# ProPrj_auduino__2024-11-21.net
KiCad netlist of a schematic drawn in EasyEDA Pro
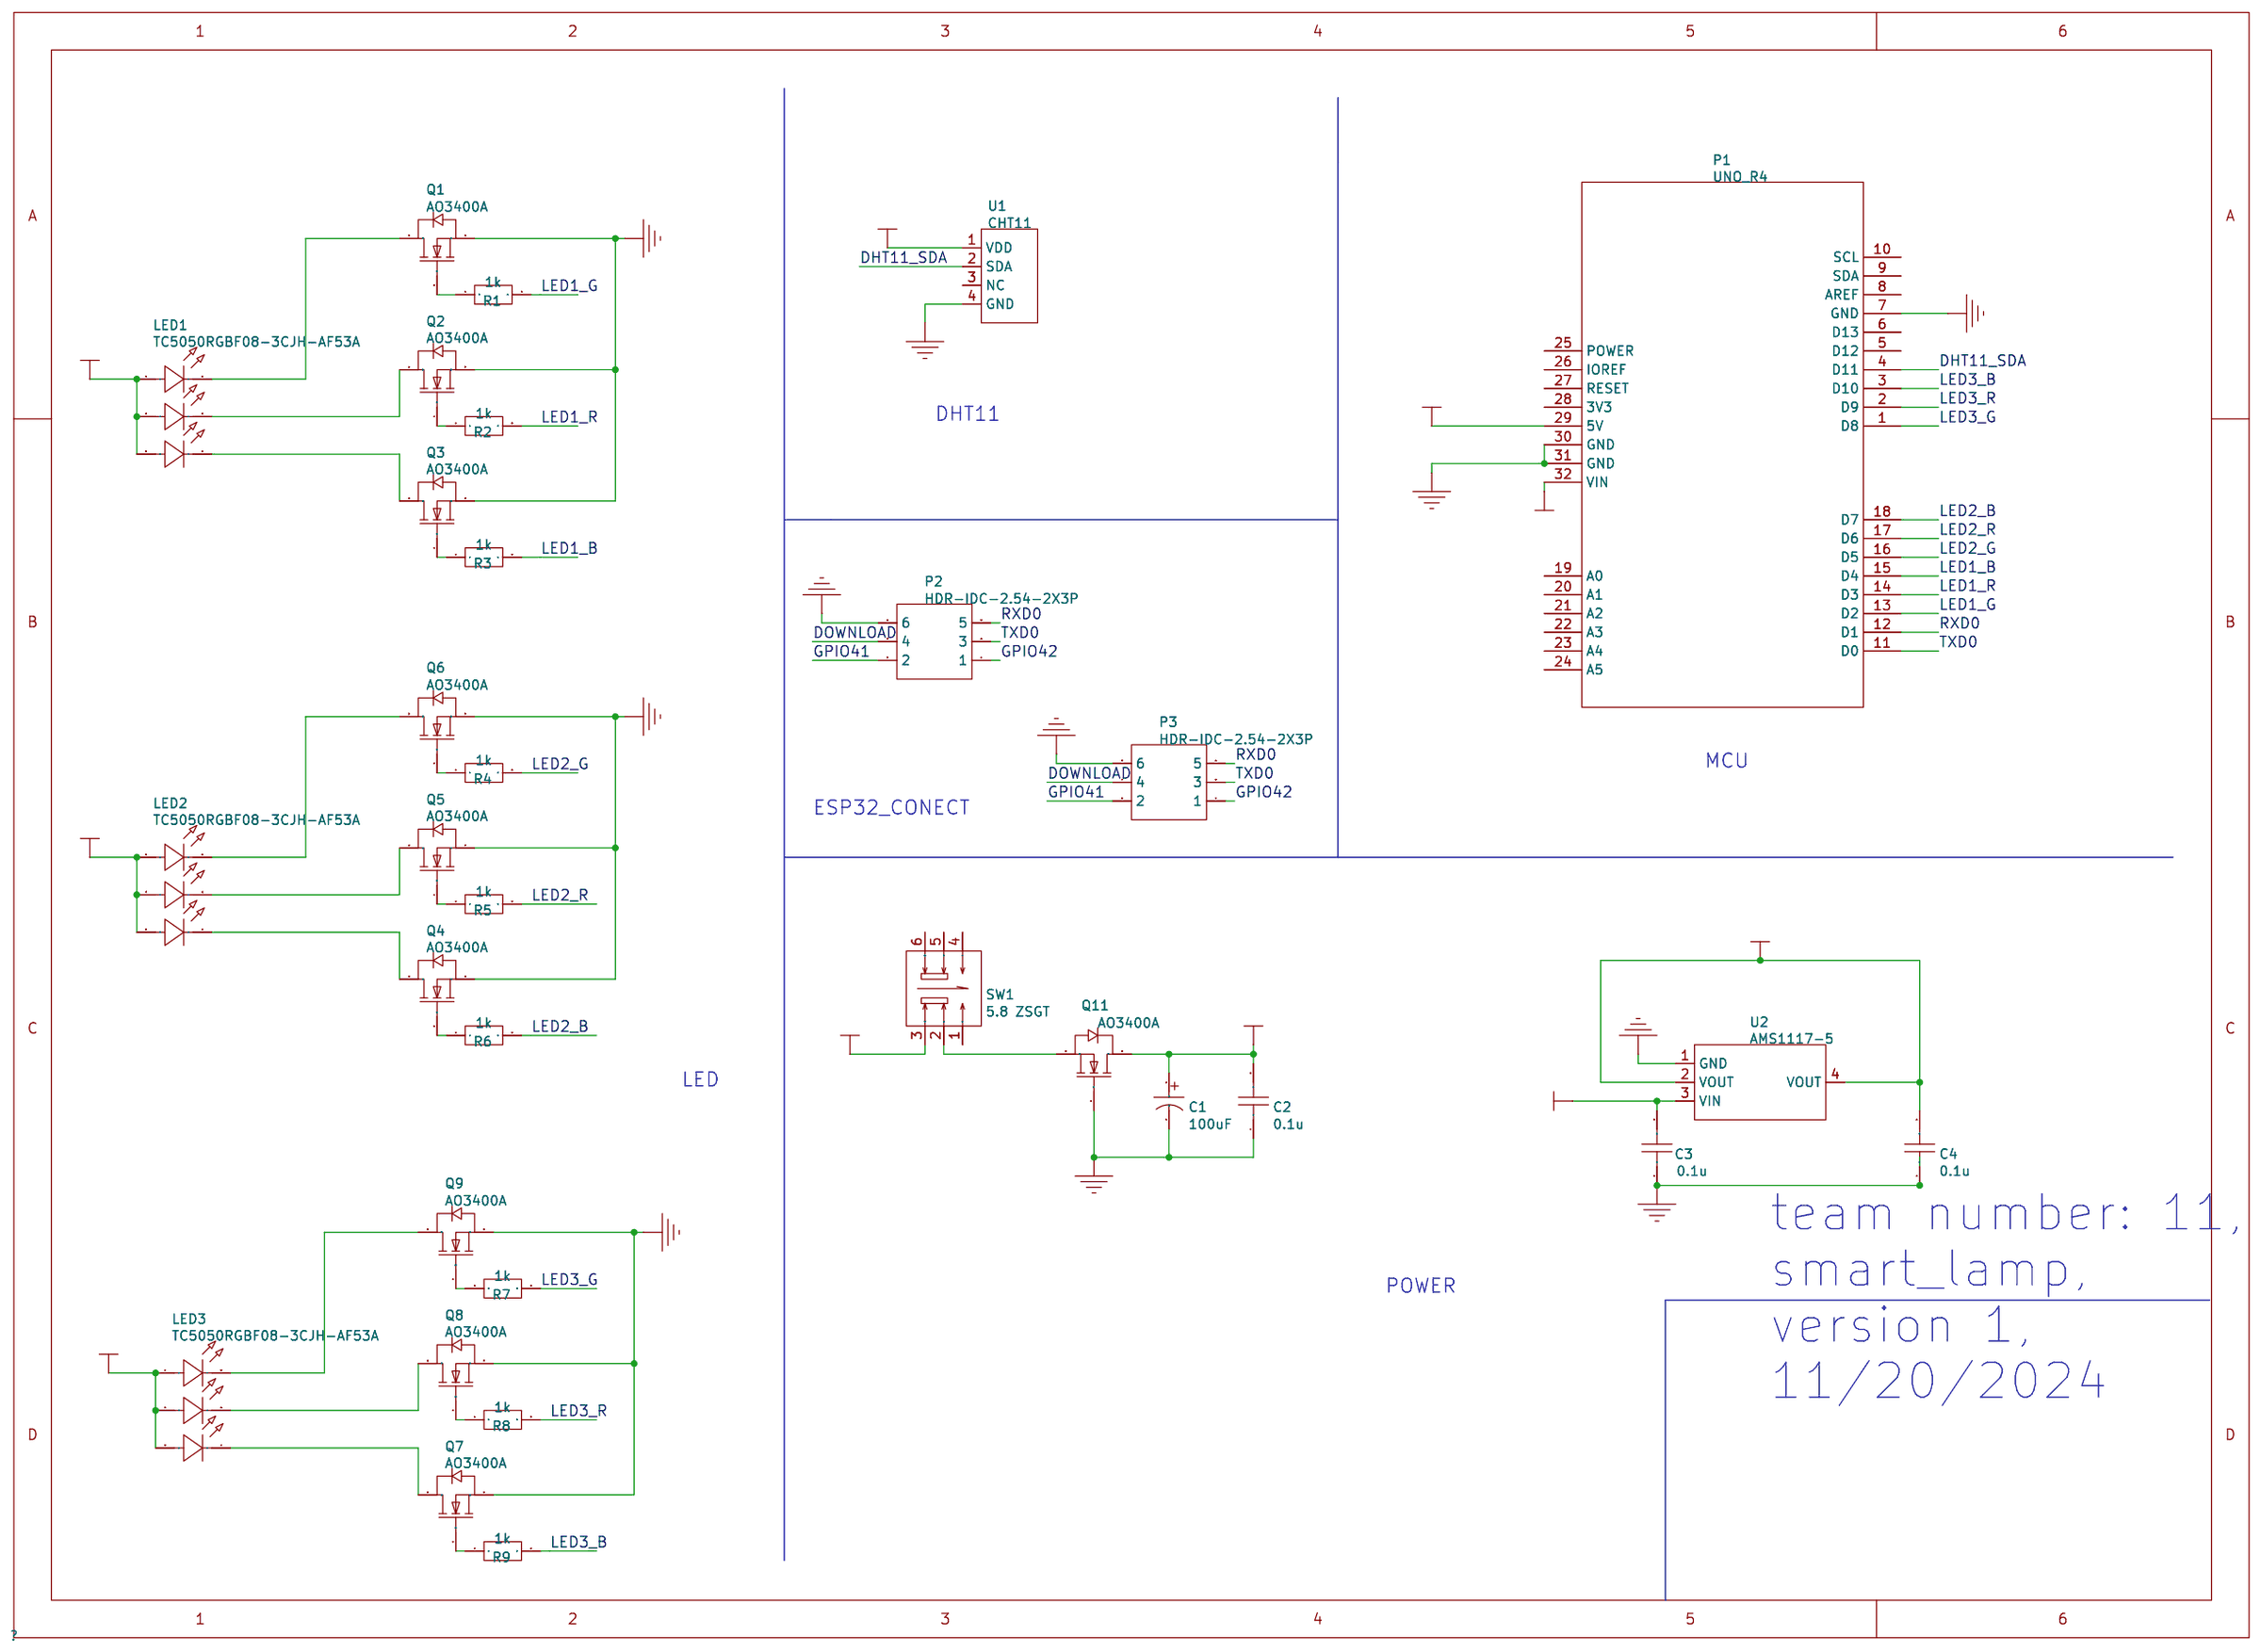
[diagram p0: schematic sheet]

(export (version "E")
  (design (tool "Eeschema 10.0.6"))
  (components
    (comp (ref "C1")
      (value "100uF")
      (footprint "easyedapro:CAP-TH_BD6.3-P2.50-D1.0-FD")
      (fields
        (field (name "Manufacturer Part") "GR107V025E11RR0VH4FP0")
        (field (name "Manufacturer") "CX(承兴)")
      )
      (libsource (lib "easyedapro") (part "100uF"))
    )
    (comp (ref "C2")
      (value "0.1u")
      (footprint "easyedapro:C0603")
      (libsource (lib "easyedapro") (part "0.1u"))
    )
    (comp (ref "C3")
      (value "0.1u")
      (footprint "easyedapro:C0603")
      (libsource (lib "easyedapro") (part "0.1u"))
    )
    (comp (ref "C4")
      (value "0.1u")
      (footprint "easyedapro:C0603")
      (libsource (lib "easyedapro") (part "0.1u"))
    )
    (comp (ref "LED1")
      (value "TC5050RGBF08-3CJH-AF53A")
      (footprint "easyedapro:LED-SMD_6P-L5.0-W5.0-TL_TC5050RGBF08")
      (fields (field (name "Manufacturer") "TCWIN(天成)"))
      (libsource (lib "easyedapro") (part "TC5050RGBF08-3CJH-AF53A"))
    )
    (comp (ref "LED2")
      (value "TC5050RGBF08-3CJH-AF53A")
      (footprint "easyedapro:LED-SMD_6P-L5.0-W5.0-TL_TC5050RGBF08")
      (fields (field (name "Manufacturer") "TCWIN(天成)"))
      (libsource (lib "easyedapro") (part "TC5050RGBF08-3CJH-AF53A"))
    )
    (comp (ref "LED3")
      (value "TC5050RGBF08-3CJH-AF53A")
      (footprint "easyedapro:LED-SMD_6P-L5.0-W5.0-TL_TC5050RGBF08")
      (fields (field (name "Manufacturer") "TCWIN(天成)"))
      (libsource (lib "easyedapro") (part "TC5050RGBF08-3CJH-AF53A"))
    )
    (comp (ref "P1")
      (value "UNO_R4")
      (footprint "easyedapro:UNO_R3")
      (libsource (lib "easyedapro") (part "UNO_R3"))
    )
    (comp (ref "P2")
      (value "HDR-IDC-2.54-2X3P")
      (footprint "easyedapro:HDR-M-2.54_2X3")
      (fields (field (name "Manufacturer Part") "2X3 2.54mm IDC Box") (field (name "Manufacturer") "BOOMELE"))
      (libsource (lib "easyedapro") (part "HDR-IDC-2.54-2X3P"))
    )
    (comp (ref "P3")
      (value "HDR-IDC-2.54-2X3P")
      (footprint "easyedapro:HDR-M-2.54_2X3")
      (fields (field (name "Manufacturer Part") "2X3 2.54mm IDC Box") (field (name "Manufacturer") "BOOMELE"))
      (libsource (lib "easyedapro") (part "HDR-IDC-2.54-2X3P"))
    )
    (comp (ref "Q1")
      (value "AO3400A")
      (footprint "easyedapro:SOT-23-3_L2.9-W1.3-P1.90-LS2.4-BR")
      (fields (field (name "Manufacturer") "AOS"))
      (libsource (lib "easyedapro") (part "AO3400A"))
    )
    (comp (ref "Q2")
      (value "AO3400A")
      (footprint "easyedapro:SOT-23-3_L2.9-W1.3-P1.90-LS2.4-BR")
      (fields (field (name "Manufacturer") "AOS"))
      (libsource (lib "easyedapro") (part "AO3400A"))
    )
    (comp (ref "Q3")
      (value "AO3400A")
      (footprint "easyedapro:SOT-23-3_L2.9-W1.3-P1.90-LS2.4-BR")
      (fields (field (name "Manufacturer") "AOS"))
      (libsource (lib "easyedapro") (part "AO3400A"))
    )
    (comp (ref "Q4")
      (value "AO3400A")
      (footprint "easyedapro:SOT-23-3_L2.9-W1.3-P1.90-LS2.4-BR")
      (fields (field (name "Manufacturer") "AOS"))
      (libsource (lib "easyedapro") (part "AO3400A"))
    )
    (comp (ref "Q5")
      (value "AO3400A")
      (footprint "easyedapro:SOT-23-3_L2.9-W1.3-P1.90-LS2.4-BR")
      (fields (field (name "Manufacturer") "AOS"))
      (libsource (lib "easyedapro") (part "AO3400A"))
    )
    (comp (ref "Q6")
      (value "AO3400A")
      (footprint "easyedapro:SOT-23-3_L2.9-W1.3-P1.90-LS2.4-BR")
      (fields (field (name "Manufacturer") "AOS"))
      (libsource (lib "easyedapro") (part "AO3400A"))
    )
    (comp (ref "Q7")
      (value "AO3400A")
      (footprint "easyedapro:SOT-23-3_L2.9-W1.3-P1.90-LS2.4-BR")
      (fields (field (name "Manufacturer") "AOS"))
      (libsource (lib "easyedapro") (part "AO3400A"))
    )
    (comp (ref "Q8")
      (value "AO3400A")
      (footprint "easyedapro:SOT-23-3_L2.9-W1.3-P1.90-LS2.4-BR")
      (fields (field (name "Manufacturer") "AOS"))
      (libsource (lib "easyedapro") (part "AO3400A"))
    )
    (comp (ref "Q9")
      (value "AO3400A")
      (footprint "easyedapro:SOT-23-3_L2.9-W1.3-P1.90-LS2.4-BR")
      (fields (field (name "Manufacturer") "AOS"))
      (libsource (lib "easyedapro") (part "AO3400A"))
    )
    (comp (ref "Q11")
      (value "AO3400A")
      (footprint "easyedapro:SOT-23-3_L2.9-W1.3-P1.90-LS2.4-BR")
      (fields (field (name "Manufacturer") "AOS"))
      (libsource (lib "") (part "AO3400A_1"))
    )
    (comp (ref "R1") (value "1k") (footprint "easyedapro:R0603") (libsource (lib "easyedapro") (part "1k")))
    (comp (ref "R2") (value "1k") (footprint "easyedapro:R0603") (libsource (lib "easyedapro") (part "1k")))
    (comp (ref "R3") (value "1k") (footprint "easyedapro:R0603") (libsource (lib "easyedapro") (part "1k")))
    (comp (ref "R4") (value "1k") (footprint "easyedapro:R0603") (libsource (lib "easyedapro") (part "1k")))
    (comp (ref "R5") (value "1k") (footprint "easyedapro:R0603") (libsource (lib "easyedapro") (part "1k")))
    (comp (ref "R6") (value "1k") (footprint "easyedapro:R0603") (libsource (lib "easyedapro") (part "1k")))
    (comp (ref "R7") (value "1k") (footprint "easyedapro:R0603") (libsource (lib "easyedapro") (part "1k")))
    (comp (ref "R8") (value "1k") (footprint "easyedapro:R0603") (libsource (lib "easyedapro") (part "1k")))
    (comp (ref "R9") (value "1k") (footprint "easyedapro:R0603") (libsource (lib "easyedapro") (part "1k")))
    (comp (ref "SW1")
      (value "5.8 ZSGT")
      (footprint "easyedapro:SW-TH_5.8ZSGT")
      (fields (field (name "Manufacturer") "SHOU HAN(首韩)"))
      (libsource (lib "easyedapro") (part "5.8 ZSGT"))
    )
    (comp (ref "U1")
      (value "CHT11")
      (footprint "easyedapro:footprint_0751")
      (fields (field (name "Manufacturer") "CYBERSEN(西博臣)"))
      (libsource (lib "easyedapro") (part "CHT11"))
    )
    (comp (ref "U2")
      (value "AMS1117-5")
      (footprint "easyedapro:SOT-223-3_L6.5-W3.4-P2.30-LS7.0-BR")
      (fields (field (name "Manufacturer Part") "AMS1117-3.3") (field (name "Manufacturer") "AMS"))
      (libsource (lib "easyedapro") (part "AMS1117-5"))
    )
  )
  (nets
    (net (code "1") (name "+5V") (class "Default")
      (node (ref "C4") (pin "2") (pinfunction "2_2") (pintype "unspecified"))
      (node (ref "LED1") (pin "1") (pinfunction "+_1") (pintype "unspecified"))
      (node (ref "LED1") (pin "2") (pinfunction "+_2") (pintype "unspecified"))
      (node (ref "LED1") (pin "3") (pinfunction "+_3") (pintype "unspecified"))
      (node (ref "LED2") (pin "1") (pinfunction "+_1") (pintype "unspecified"))
      (node (ref "LED2") (pin "2") (pinfunction "+_2") (pintype "unspecified"))
      (node (ref "LED2") (pin "3") (pinfunction "+_3") (pintype "unspecified"))
      (node (ref "LED3") (pin "1") (pinfunction "+_1") (pintype "unspecified"))
      (node (ref "LED3") (pin "2") (pinfunction "+_2") (pintype "unspecified"))
      (node (ref "LED3") (pin "3") (pinfunction "+_3") (pintype "unspecified"))
      (node (ref "P1") (pin "29") (pinfunction "5V_29") (pintype "unspecified"))
      (node (ref "U1") (pin "1") (pinfunction "VDD_1") (pintype "unspecified"))
      (node (ref "U2") (pin "2") (pinfunction "VOUT_2") (pintype "unspecified"))
      (node (ref "U2") (pin "4") (pinfunction "VOUT_4") (pintype "unspecified"))
    )
    (net (code "2") (name "/DHT11_SDA") (class "Default")
      (node (ref "P1") (pin "4") (pinfunction "D11_4") (pintype "unspecified"))
      (node (ref "U1") (pin "2") (pinfunction "SDA_2") (pintype "unspecified"))
    )
    (net (code "3") (name "/DOWNLOAD") (class "Default")
      (node (ref "P2") (pin "4") (pinfunction "4_4") (pintype "unspecified"))
      (node (ref "P3") (pin "4") (pinfunction "4_4") (pintype "unspecified"))
    )
    (net (code "4") (name "/GPIO41") (class "Default")
      (node (ref "P2") (pin "2") (pinfunction "2_2") (pintype "unspecified"))
      (node (ref "P3") (pin "2") (pinfunction "2_2") (pintype "unspecified"))
    )
    (net (code "5") (name "/GPIO42") (class "Default")
      (node (ref "P2") (pin "1") (pinfunction "1_1") (pintype "unspecified"))
      (node (ref "P3") (pin "1") (pinfunction "1_1") (pintype "unspecified"))
    )
    (net (code "6") (name "/LED1_B") (class "Default")
      (node (ref "P1") (pin "15") (pinfunction "D4_15") (pintype "unspecified"))
      (node (ref "R3") (pin "2") (pinfunction "2_2") (pintype "unspecified"))
    )
    (net (code "7") (name "/LED1_G") (class "Default")
      (node (ref "P1") (pin "13") (pinfunction "D2_13") (pintype "unspecified"))
      (node (ref "R1") (pin "2") (pinfunction "2_2") (pintype "unspecified"))
    )
    (net (code "8") (name "/LED1_R") (class "Default")
      (node (ref "P1") (pin "14") (pinfunction "D3_14") (pintype "unspecified"))
      (node (ref "R2") (pin "2") (pinfunction "2_2") (pintype "unspecified"))
    )
    (net (code "9") (name "/LED2_B") (class "Default")
      (node (ref "P1") (pin "18") (pinfunction "D7_18") (pintype "unspecified"))
      (node (ref "R6") (pin "2") (pinfunction "2_2") (pintype "unspecified"))
    )
    (net (code "10") (name "/LED2_G") (class "Default")
      (node (ref "P1") (pin "16") (pinfunction "D5_16") (pintype "unspecified"))
      (node (ref "R4") (pin "2") (pinfunction "2_2") (pintype "unspecified"))
    )
    (net (code "11") (name "/LED2_R") (class "Default")
      (node (ref "P1") (pin "17") (pinfunction "D6_17") (pintype "unspecified"))
      (node (ref "R5") (pin "2") (pinfunction "2_2") (pintype "unspecified"))
    )
    (net (code "12") (name "/LED3_B") (class "Default")
      (node (ref "P1") (pin "3") (pinfunction "D10_3") (pintype "unspecified"))
      (node (ref "R9") (pin "2") (pinfunction "2_2") (pintype "unspecified"))
    )
    (net (code "13") (name "/LED3_G") (class "Default")
      (node (ref "P1") (pin "1") (pinfunction "D8_1") (pintype "unspecified"))
      (node (ref "R7") (pin "2") (pinfunction "2_2") (pintype "unspecified"))
    )
    (net (code "14") (name "/LED3_R") (class "Default")
      (node (ref "P1") (pin "2") (pinfunction "D9_2") (pintype "unspecified"))
      (node (ref "R8") (pin "2") (pinfunction "2_2") (pintype "unspecified"))
    )
    (net (code "15") (name "/RXD0") (class "Default")
      (node (ref "P1") (pin "12") (pinfunction "D1_12") (pintype "unspecified"))
      (node (ref "P2") (pin "5") (pinfunction "5_5") (pintype "unspecified"))
      (node (ref "P3") (pin "5") (pinfunction "5_5") (pintype "unspecified"))
    )
    (net (code "16") (name "/TXD0") (class "Default")
      (node (ref "P1") (pin "11") (pinfunction "D0_11") (pintype "unspecified"))
      (node (ref "P2") (pin "3") (pinfunction "3_3") (pintype "unspecified"))
      (node (ref "P3") (pin "3") (pinfunction "3_3") (pintype "unspecified"))
    )
    (net (code "17") (name "GND") (class "Default")
      (node (ref "C1") (pin "2") (pinfunction "2_2") (pintype "unspecified"))
      (node (ref "C2") (pin "1") (pinfunction "1_1") (pintype "unspecified"))
      (node (ref "C3") (pin "1") (pinfunction "1_1") (pintype "unspecified"))
      (node (ref "C4") (pin "1") (pinfunction "1_1") (pintype "unspecified"))
      (node (ref "P1") (pin "30") (pinfunction "GND_30") (pintype "unspecified"))
      (node (ref "P1") (pin "31") (pinfunction "GND_31") (pintype "unspecified"))
      (node (ref "P1") (pin "7") (pinfunction "GND_7") (pintype "unspecified"))
      (node (ref "P2") (pin "6") (pinfunction "6_6") (pintype "unspecified"))
      (node (ref "P3") (pin "6") (pinfunction "6_6") (pintype "unspecified"))
      (node (ref "Q1") (pin "2") (pinfunction "S_2") (pintype "unspecified"))
      (node (ref "Q11") (pin "1") (pinfunction "G_1") (pintype "unspecified"))
      (node (ref "Q2") (pin "2") (pinfunction "S_2") (pintype "unspecified"))
      (node (ref "Q3") (pin "2") (pinfunction "S_2") (pintype "unspecified"))
      (node (ref "Q4") (pin "2") (pinfunction "S_2") (pintype "unspecified"))
      (node (ref "Q5") (pin "2") (pinfunction "S_2") (pintype "unspecified"))
      (node (ref "Q6") (pin "2") (pinfunction "S_2") (pintype "unspecified"))
      (node (ref "Q7") (pin "2") (pinfunction "S_2") (pintype "unspecified"))
      (node (ref "Q8") (pin "2") (pinfunction "S_2") (pintype "unspecified"))
      (node (ref "Q9") (pin "2") (pinfunction "S_2") (pintype "unspecified"))
      (node (ref "U1") (pin "4") (pinfunction "GND_4") (pintype "unspecified"))
      (node (ref "U2") (pin "1") (pinfunction "GND_1") (pintype "unspecified"))
    )
    (net (code "18") (name "Net-(Q1-D)") (class "Default")
      (node (ref "LED1") (pin "6") (pinfunction "-_6") (pintype "unspecified"))
      (node (ref "Q1") (pin "3") (pinfunction "D_3") (pintype "unspecified"))
    )
    (net (code "19") (name "Net-(Q1-G)") (class "Default")
      (node (ref "Q1") (pin "1") (pinfunction "G_1") (pintype "unspecified"))
      (node (ref "R1") (pin "1") (pinfunction "1_1") (pintype "unspecified"))
    )
    (net (code "20") (name "Net-(Q2-D)") (class "Default")
      (node (ref "LED1") (pin "5") (pinfunction "-_5") (pintype "unspecified"))
      (node (ref "Q2") (pin "3") (pinfunction "D_3") (pintype "unspecified"))
    )
    (net (code "21") (name "Net-(Q2-G)") (class "Default")
      (node (ref "Q2") (pin "1") (pinfunction "G_1") (pintype "unspecified"))
      (node (ref "R2") (pin "1") (pinfunction "1_1") (pintype "unspecified"))
    )
    (net (code "22") (name "Net-(Q3-D)") (class "Default")
      (node (ref "LED1") (pin "4") (pinfunction "-_4") (pintype "unspecified"))
      (node (ref "Q3") (pin "3") (pinfunction "D_3") (pintype "unspecified"))
    )
    (net (code "23") (name "Net-(Q3-G)") (class "Default")
      (node (ref "Q3") (pin "1") (pinfunction "G_1") (pintype "unspecified"))
      (node (ref "R3") (pin "1") (pinfunction "1_1") (pintype "unspecified"))
    )
    (net (code "24") (name "Net-(Q4-D)") (class "Default")
      (node (ref "LED2") (pin "4") (pinfunction "-_4") (pintype "unspecified"))
      (node (ref "Q4") (pin "3") (pinfunction "D_3") (pintype "unspecified"))
    )
    (net (code "25") (name "Net-(Q4-G)") (class "Default")
      (node (ref "Q4") (pin "1") (pinfunction "G_1") (pintype "unspecified"))
      (node (ref "R6") (pin "1") (pinfunction "1_1") (pintype "unspecified"))
    )
    (net (code "26") (name "Net-(Q5-D)") (class "Default")
      (node (ref "LED2") (pin "5") (pinfunction "-_5") (pintype "unspecified"))
      (node (ref "Q5") (pin "3") (pinfunction "D_3") (pintype "unspecified"))
    )
    (net (code "27") (name "Net-(Q5-G)") (class "Default")
      (node (ref "Q5") (pin "1") (pinfunction "G_1") (pintype "unspecified"))
      (node (ref "R5") (pin "1") (pinfunction "1_1") (pintype "unspecified"))
    )
    (net (code "28") (name "Net-(Q6-D)") (class "Default")
      (node (ref "LED2") (pin "6") (pinfunction "-_6") (pintype "unspecified"))
      (node (ref "Q6") (pin "3") (pinfunction "D_3") (pintype "unspecified"))
    )
    (net (code "29") (name "Net-(Q6-G)") (class "Default")
      (node (ref "Q6") (pin "1") (pinfunction "G_1") (pintype "unspecified"))
      (node (ref "R4") (pin "1") (pinfunction "1_1") (pintype "unspecified"))
    )
    (net (code "30") (name "Net-(Q7-D)") (class "Default")
      (node (ref "LED3") (pin "4") (pinfunction "-_4") (pintype "unspecified"))
      (node (ref "Q7") (pin "3") (pinfunction "D_3") (pintype "unspecified"))
    )
    (net (code "31") (name "Net-(Q7-G)") (class "Default")
      (node (ref "Q7") (pin "1") (pinfunction "G_1") (pintype "unspecified"))
      (node (ref "R9") (pin "1") (pinfunction "1_1") (pintype "unspecified"))
    )
    (net (code "32") (name "Net-(Q8-D)") (class "Default")
      (node (ref "LED3") (pin "5") (pinfunction "-_5") (pintype "unspecified"))
      (node (ref "Q8") (pin "3") (pinfunction "D_3") (pintype "unspecified"))
    )
    (net (code "33") (name "Net-(Q8-G)") (class "Default")
      (node (ref "Q8") (pin "1") (pinfunction "G_1") (pintype "unspecified"))
      (node (ref "R8") (pin "1") (pinfunction "1_1") (pintype "unspecified"))
    )
    (net (code "34") (name "Net-(Q9-D)") (class "Default")
      (node (ref "LED3") (pin "6") (pinfunction "-_6") (pintype "unspecified"))
      (node (ref "Q9") (pin "3") (pinfunction "D_3") (pintype "unspecified"))
    )
    (net (code "35") (name "Net-(Q9-G)") (class "Default")
      (node (ref "Q9") (pin "1") (pinfunction "G_1") (pintype "unspecified"))
      (node (ref "R7") (pin "1") (pinfunction "1_1") (pintype "unspecified"))
    )
    (net (code "36") (name "Net-(Q11-S)") (class "Default")
      (node (ref "Q11") (pin "2") (pinfunction "S_2") (pintype "unspecified"))
      (node (ref "SW1") (pin "2") (pinfunction "2_2") (pintype "unspecified"))
    )
    (net (code "37") (name "VBAT") (class "Default")
      (node (ref "C1") (pin "1") (pinfunction "1_1") (pintype "unspecified"))
      (node (ref "C2") (pin "2") (pinfunction "2_2") (pintype "unspecified"))
      (node (ref "C3") (pin "2") (pinfunction "2_2") (pintype "unspecified"))
      (node (ref "Q11") (pin "3") (pinfunction "D_3") (pintype "unspecified"))
      (node (ref "U2") (pin "3") (pinfunction "VIN_3") (pintype "unspecified"))
    )
    (net (code "38") (name "VIN") (class "Default")
      (node (ref "P1") (pin "32") (pinfunction "VIN_32") (pintype "unspecified"))
      (node (ref "SW1") (pin "3") (pinfunction "3_3") (pintype "unspecified"))
    )
    (net (code "39") (name "unconnected-(P1-3V3-Pad28)") (class "Default")
      (node (ref "P1") (pin "28") (pinfunction "3V3_28") (pintype "unspecified"))
    )
    (net (code "40") (name "unconnected-(P1-A0-Pad19)") (class "Default")
      (node (ref "P1") (pin "19") (pinfunction "A0_19") (pintype "unspecified"))
    )
    (net (code "41") (name "unconnected-(P1-A1-Pad20)") (class "Default")
      (node (ref "P1") (pin "20") (pinfunction "A1_20") (pintype "unspecified"))
    )
    (net (code "42") (name "unconnected-(P1-A2-Pad21)") (class "Default")
      (node (ref "P1") (pin "21") (pinfunction "A2_21") (pintype "unspecified"))
    )
    (net (code "43") (name "unconnected-(P1-A3-Pad22)") (class "Default")
      (node (ref "P1") (pin "22") (pinfunction "A3_22") (pintype "unspecified"))
    )
    (net (code "44") (name "unconnected-(P1-A4-Pad23)") (class "Default")
      (node (ref "P1") (pin "23") (pinfunction "A4_23") (pintype "unspecified"))
    )
    (net (code "45") (name "unconnected-(P1-A5-Pad24)") (class "Default")
      (node (ref "P1") (pin "24") (pinfunction "A5_24") (pintype "unspecified"))
    )
    (net (code "46") (name "unconnected-(P1-AREF-Pad8)") (class "Default")
      (node (ref "P1") (pin "8") (pinfunction "AREF_8") (pintype "unspecified"))
    )
    (net (code "47") (name "unconnected-(P1-D12-Pad5)") (class "Default")
      (node (ref "P1") (pin "5") (pinfunction "D12_5") (pintype "unspecified"))
    )
    (net (code "48") (name "unconnected-(P1-D13-Pad6)") (class "Default")
      (node (ref "P1") (pin "6") (pinfunction "D13_6") (pintype "unspecified"))
    )
    (net (code "49") (name "unconnected-(P1-IOREF-Pad26)") (class "Default")
      (node (ref "P1") (pin "26") (pinfunction "IOREF_26") (pintype "unspecified"))
    )
    (net (code "50") (name "unconnected-(P1-POWER-Pad25)") (class "Default")
      (node (ref "P1") (pin "25") (pinfunction "POWER_25") (pintype "unspecified"))
    )
    (net (code "51") (name "unconnected-(P1-RESET-Pad27)") (class "Default")
      (node (ref "P1") (pin "27") (pinfunction "RESET_27") (pintype "unspecified"))
    )
    (net (code "52") (name "unconnected-(P1-SCL-Pad10)") (class "Default")
      (node (ref "P1") (pin "10") (pinfunction "SCL_10") (pintype "unspecified"))
    )
    (net (code "53") (name "unconnected-(P1-SDA-Pad9)") (class "Default")
      (node (ref "P1") (pin "9") (pinfunction "SDA_9") (pintype "unspecified"))
    )
    (net (code "54") (name "unconnected-(SW1-Pad1)") (class "Default")
      (node (ref "SW1") (pin "1") (pinfunction "1_1") (pintype "unspecified"))
    )
    (net (code "55") (name "unconnected-(SW1-Pad4)") (class "Default")
      (node (ref "SW1") (pin "4") (pinfunction "4_4") (pintype "unspecified"))
    )
    (net (code "56") (name "unconnected-(SW1-Pad5)") (class "Default")
      (node (ref "SW1") (pin "5") (pinfunction "5_5") (pintype "unspecified"))
    )
    (net (code "57") (name "unconnected-(SW1-Pad6)") (class "Default")
      (node (ref "SW1") (pin "6") (pinfunction "6_6") (pintype "unspecified"))
    )
    (net (code "58") (name "unconnected-(U1-NC-Pad3)") (class "Default")
      (node (ref "U1") (pin "3") (pinfunction "NC_3") (pintype "unspecified"))
    )
  )
)
